# RoverBaseboard.net
KiCad netlist of a schematic drawn in EAGLE
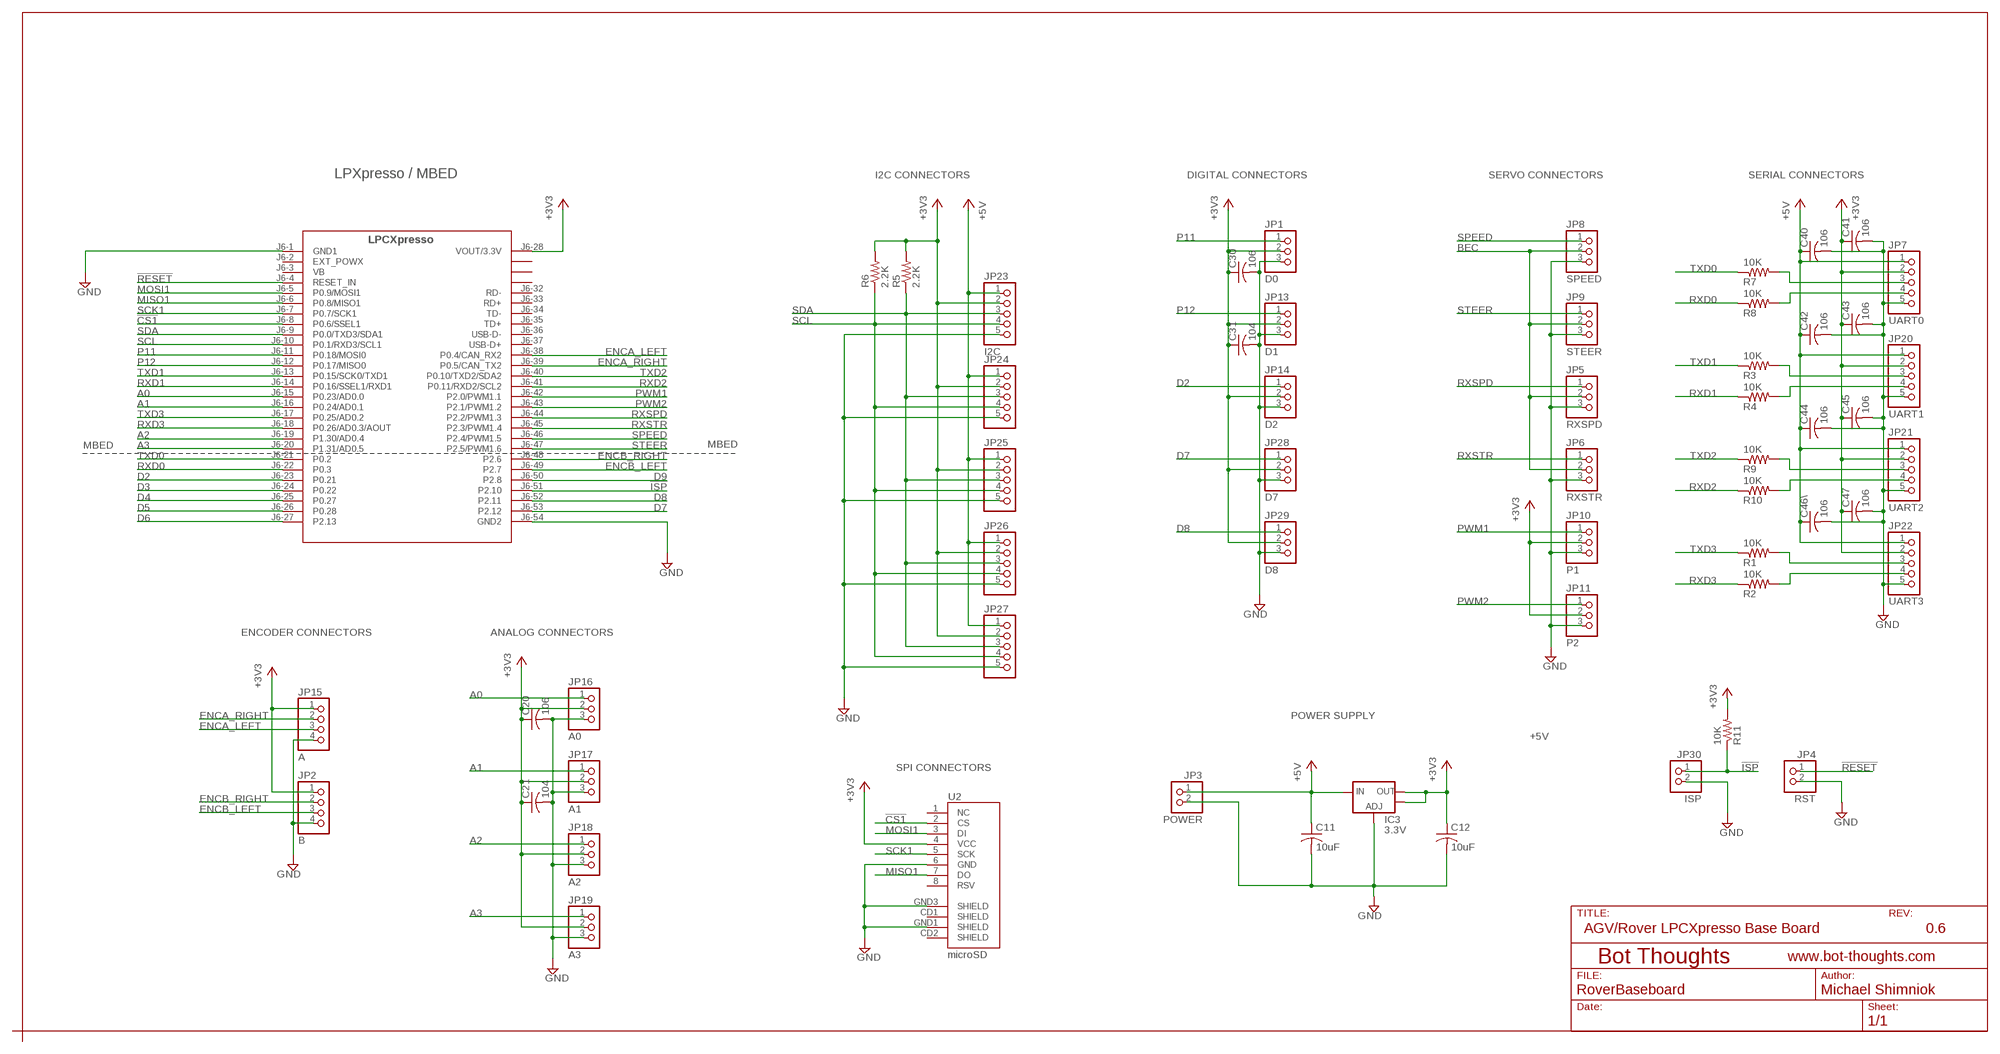
[diagram p0: schematic, sheet 1]

(export (version "E")
  (design (tool "Eeschema 10.0.6"))
  (components
    (comp (ref "C11")
      (value "10uF")
      (footprint "eagle-import:C1206")
      (libsource (lib "eagle-import") (part "C-USC1206"))
    )
    (comp (ref "C12")
      (value "10uF")
      (footprint "eagle-import:C1206")
      (libsource (lib "eagle-import") (part "C-USC1206"))
    )
    (comp (ref "C20")
      (value "106")
      (footprint "eagle-import:C0603")
      (libsource (lib "eagle-import") (part "C-USC0603"))
    )
    (comp (ref "C21")
      (value "104")
      (footprint "eagle-import:C0603")
      (libsource (lib "eagle-import") (part "C-USC0603"))
    )
    (comp (ref "C30")
      (value "106")
      (footprint "eagle-import:C0603")
      (libsource (lib "eagle-import") (part "C-USC0603"))
    )
    (comp (ref "C31")
      (value "104")
      (footprint "eagle-import:C0603")
      (libsource (lib "eagle-import") (part "C-USC0603"))
    )
    (comp (ref "C40")
      (value "106")
      (footprint "eagle-import:C0603")
      (libsource (lib "eagle-import") (part "C-USC0603"))
    )
    (comp (ref "C41")
      (value "106")
      (footprint "eagle-import:C0603")
      (libsource (lib "eagle-import") (part "C-USC0603"))
    )
    (comp (ref "C42")
      (value "106")
      (footprint "eagle-import:C0603")
      (libsource (lib "eagle-import") (part "C-USC0603"))
    )
    (comp (ref "C43")
      (value "106")
      (footprint "eagle-import:C0603")
      (libsource (lib "eagle-import") (part "C-USC0603"))
    )
    (comp (ref "C44")
      (value "106")
      (footprint "eagle-import:C0603")
      (libsource (lib "eagle-import") (part "C-USC0603"))
    )
    (comp (ref "C45")
      (value "106")
      (footprint "eagle-import:C0603")
      (libsource (lib "eagle-import") (part "C-USC0603"))
    )
    (comp (ref "C46\\")
      (value "106")
      (footprint "eagle-import:C0603")
      (libsource (lib "eagle-import") (part "C-USC0603"))
    )
    (comp (ref "C47")
      (value "106")
      (footprint "eagle-import:C0603")
      (libsource (lib "eagle-import") (part "C-USC0603"))
    )
    (comp (ref "IC3")
      (value "3.3V")
      (footprint "eagle-import:SOT223")
      (libsource (lib "eagle-import") (part "V_REG_LM1117SOT223"))
    )
    (comp (ref "JP1")
      (value "D0")
      (footprint "eagle-import:1X03-S")
      (libsource (lib "eagle-import") (part "PINHD-1X03_2.54-S"))
    )
    (comp (ref "JP2")
      (value "B")
      (footprint "eagle-import:1X04-S")
      (libsource (lib "eagle-import") (part "PINHD-1X04_2.54-S"))
    )
    (comp (ref "JP3")
      (value "POWER")
      (footprint "eagle-import:1X02-S")
      (libsource (lib "eagle-import") (part "PINHD-1X02_2.54-S"))
    )
    (comp (ref "JP4")
      (value "RST")
      (footprint "eagle-import:1X02-S")
      (libsource (lib "eagle-import") (part "PINHD-1X02_2.54-S"))
    )
    (comp (ref "JP5")
      (value "RXSPD")
      (footprint "eagle-import:1X03-S")
      (libsource (lib "eagle-import") (part "PINHD-1X03_2.54-S"))
    )
    (comp (ref "JP6")
      (value "RXSTR")
      (footprint "eagle-import:1X03-S")
      (libsource (lib "eagle-import") (part "PINHD-1X03_2.54-S"))
    )
    (comp (ref "JP7")
      (value "UART0")
      (footprint "eagle-import:1X05-S")
      (libsource (lib "eagle-import") (part "PINHD-1X05_2.54-S"))
    )
    (comp (ref "JP8")
      (value "SPEED")
      (footprint "eagle-import:1X03-S")
      (libsource (lib "eagle-import") (part "PINHD-1X03_2.54-S"))
    )
    (comp (ref "JP9")
      (value "STEER")
      (footprint "eagle-import:1X03-S")
      (libsource (lib "eagle-import") (part "PINHD-1X03_2.54-S"))
    )
    (comp (ref "JP10")
      (value "P1")
      (footprint "eagle-import:1X03-S")
      (libsource (lib "eagle-import") (part "PINHD-1X03_2.54-S"))
    )
    (comp (ref "JP11")
      (value "P2")
      (footprint "eagle-import:1X03-S")
      (libsource (lib "eagle-import") (part "PINHD-1X03_2.54-S"))
    )
    (comp (ref "JP13")
      (value "D1")
      (footprint "eagle-import:1X03-S")
      (libsource (lib "eagle-import") (part "PINHD-1X03_2.54-S"))
    )
    (comp (ref "JP14")
      (value "D2")
      (footprint "eagle-import:1X03-S")
      (libsource (lib "eagle-import") (part "PINHD-1X03_2.54-S"))
    )
    (comp (ref "JP15")
      (value "A")
      (footprint "eagle-import:1X04-S")
      (libsource (lib "eagle-import") (part "PINHD-1X04_2.54-S"))
    )
    (comp (ref "JP16")
      (value "A0")
      (footprint "eagle-import:1X03-S")
      (libsource (lib "eagle-import") (part "PINHD-1X03_2.54-S"))
    )
    (comp (ref "JP17")
      (value "A1")
      (footprint "eagle-import:1X03-S")
      (libsource (lib "eagle-import") (part "PINHD-1X03_2.54-S"))
    )
    (comp (ref "JP18")
      (value "A2")
      (footprint "eagle-import:1X03-S")
      (libsource (lib "eagle-import") (part "PINHD-1X03_2.54-S"))
    )
    (comp (ref "JP19")
      (value "A3")
      (footprint "eagle-import:1X03-S")
      (libsource (lib "eagle-import") (part "PINHD-1X03_2.54-S"))
    )
    (comp (ref "JP20")
      (value "UART1")
      (footprint "eagle-import:1X05-S")
      (libsource (lib "eagle-import") (part "PINHD-1X05_2.54-S"))
    )
    (comp (ref "JP21")
      (value "UART2")
      (footprint "eagle-import:1X05-S")
      (libsource (lib "eagle-import") (part "PINHD-1X05_2.54-S"))
    )
    (comp (ref "JP22")
      (value "UART3")
      (footprint "eagle-import:1X05-S")
      (libsource (lib "eagle-import") (part "PINHD-1X05_2.54-S"))
    )
    (comp (ref "JP23")
      (value "I2C")
      (footprint "eagle-import:1X05-S")
      (libsource (lib "eagle-import") (part "PINHD-1X05_2.54-S"))
    )
    (comp (ref "JP24")
      (value "PINHD-1X05_2.54-S")
      (footprint "eagle-import:1X05-S")
      (libsource (lib "eagle-import") (part "PINHD-1X05_2.54-S"))
    )
    (comp (ref "JP25")
      (value "PINHD-1X05_2.54-S")
      (footprint "eagle-import:1X05-S")
      (libsource (lib "eagle-import") (part "PINHD-1X05_2.54-S"))
    )
    (comp (ref "JP26")
      (value "PINHD-1X05_2.54-S")
      (footprint "eagle-import:1X05-S")
      (libsource (lib "eagle-import") (part "PINHD-1X05_2.54-S"))
    )
    (comp (ref "JP27")
      (value "PINHD-1X05_2.54-S")
      (footprint "eagle-import:1X05-S")
      (libsource (lib "eagle-import") (part "PINHD-1X05_2.54-S"))
    )
    (comp (ref "JP28")
      (value "D7")
      (footprint "eagle-import:1X03-S")
      (libsource (lib "eagle-import") (part "PINHD-1X03_2.54-S"))
    )
    (comp (ref "JP29")
      (value "D8")
      (footprint "eagle-import:1X03-S")
      (libsource (lib "eagle-import") (part "PINHD-1X03_2.54-S"))
    )
    (comp (ref "JP30")
      (value "ISP")
      (footprint "eagle-import:1X02-S")
      (libsource (lib "eagle-import") (part "PINHD-1X02_2.54-S"))
    )
    (comp (ref "R1")
      (value "10K")
      (footprint "eagle-import:R0603")
      (fields (field (name "MPN") "WCR0805-220RFI"))
      (libsource (lib "eagle-import") (part "R-US_R0603"))
    )
    (comp (ref "R2")
      (value "10K")
      (footprint "eagle-import:R0603")
      (fields (field (name "MPN") "WCR0805-220RFI"))
      (libsource (lib "eagle-import") (part "R-US_R0603"))
    )
    (comp (ref "R3")
      (value "10K")
      (footprint "eagle-import:R0603")
      (fields (field (name "MPN") "WCR0805-220RFI"))
      (libsource (lib "eagle-import") (part "R-US_R0603"))
    )
    (comp (ref "R4")
      (value "10K")
      (footprint "eagle-import:R0603")
      (fields (field (name "MPN") "WCR0805-220RFI"))
      (libsource (lib "eagle-import") (part "R-US_R0603"))
    )
    (comp (ref "R5")
      (value "2.2K")
      (footprint "eagle-import:R0603")
      (libsource (lib "eagle-import") (part "R-US_R0603"))
    )
    (comp (ref "R6")
      (value "2.2K")
      (footprint "eagle-import:R0603")
      (libsource (lib "eagle-import") (part "R-US_R0603"))
    )
    (comp (ref "R7")
      (value "10K")
      (footprint "eagle-import:R0603")
      (fields (field (name "MPN") "WCR0805-220RFI"))
      (libsource (lib "eagle-import") (part "R-US_R0603"))
    )
    (comp (ref "R8")
      (value "10K")
      (footprint "eagle-import:R0603")
      (fields (field (name "MPN") "WCR0805-220RFI"))
      (libsource (lib "eagle-import") (part "R-US_R0603"))
    )
    (comp (ref "R9")
      (value "10K")
      (footprint "eagle-import:R0603")
      (fields (field (name "MPN") "WCR0805-220RFI"))
      (libsource (lib "eagle-import") (part "R-US_R0603"))
    )
    (comp (ref "R10")
      (value "10K")
      (footprint "eagle-import:R0603")
      (fields (field (name "MPN") "WCR0805-220RFI"))
      (libsource (lib "eagle-import") (part "R-US_R0603"))
    )
    (comp (ref "R11")
      (value "10K")
      (footprint "eagle-import:R0603")
      (fields (field (name "MPN") "WCR0805-220RFI"))
      (libsource (lib "eagle-import") (part "R-US_R0603"))
    )
    (comp (ref "U$1")
      (value "LPCXPRESSO")
      (footprint "eagle-import:LPCXPRESSO_NO_PAD")
      (libsource (lib "eagle-import") (part "LPCXPRESSO_NO_PAD_1768_REVB"))
    )
    (comp (ref "U2")
      (value "microSD")
      (footprint "eagle-import:MICRO-SD-SOCKET-PP")
      (libsource (lib "eagle-import") (part "USD-SOCKETNEW"))
    )
  )
  (nets
    (net (code "1") (name "+3V3") (class "Default")
      (node (ref "C12") (pin "1") (pinfunction "1_1") (pintype "passive"))
      (node (ref "C20") (pin "1") (pinfunction "1_1") (pintype "passive"))
      (node (ref "C21") (pin "1") (pinfunction "1_1") (pintype "passive"))
      (node (ref "C30") (pin "1") (pinfunction "1_1") (pintype "passive"))
      (node (ref "C31") (pin "1") (pinfunction "1_1") (pintype "passive"))
      (node (ref "C41") (pin "1") (pinfunction "1_1") (pintype "passive"))
      (node (ref "C43") (pin "1") (pinfunction "1_1") (pintype "passive"))
      (node (ref "C45") (pin "1") (pinfunction "1_1") (pintype "passive"))
      (node (ref "C47") (pin "1") (pinfunction "1_1") (pintype "passive"))
      (node (ref "IC3") (pin "2") (pinfunction "OUT_2") (pintype "output"))
      (node (ref "IC3") (pin "4") (pinfunction "OUT_4") (pintype "output"))
      (node (ref "JP1") (pin "2") (pinfunction "2_2") (pintype "passive"))
      (node (ref "JP10") (pin "2") (pinfunction "2_2") (pintype "passive"))
      (node (ref "JP11") (pin "2") (pinfunction "2_2") (pintype "passive"))
      (node (ref "JP13") (pin "2") (pinfunction "2_2") (pintype "passive"))
      (node (ref "JP14") (pin "2") (pinfunction "2_2") (pintype "passive"))
      (node (ref "JP15") (pin "1") (pinfunction "1_1") (pintype "passive"))
      (node (ref "JP16") (pin "2") (pinfunction "2_2") (pintype "passive"))
      (node (ref "JP17") (pin "2") (pinfunction "2_2") (pintype "passive"))
      (node (ref "JP18") (pin "2") (pinfunction "2_2") (pintype "passive"))
      (node (ref "JP19") (pin "2") (pinfunction "2_2") (pintype "passive"))
      (node (ref "JP2") (pin "1") (pinfunction "1_1") (pintype "passive"))
      (node (ref "JP20") (pin "2") (pinfunction "2_2") (pintype "passive"))
      (node (ref "JP21") (pin "2") (pinfunction "2_2") (pintype "passive"))
      (node (ref "JP22") (pin "2") (pinfunction "2_2") (pintype "passive"))
      (node (ref "JP23") (pin "2") (pinfunction "2_2") (pintype "passive"))
      (node (ref "JP24") (pin "2") (pinfunction "2_2") (pintype "passive"))
      (node (ref "JP25") (pin "2") (pinfunction "2_2") (pintype "passive"))
      (node (ref "JP26") (pin "2") (pinfunction "2_2") (pintype "passive"))
      (node (ref "JP27") (pin "2") (pinfunction "2_2") (pintype "passive"))
      (node (ref "JP28") (pin "2") (pinfunction "2_2") (pintype "passive"))
      (node (ref "JP29") (pin "2") (pinfunction "2_2") (pintype "passive"))
      (node (ref "JP7") (pin "2") (pinfunction "2_2") (pintype "passive"))
      (node (ref "R11") (pin "2") (pinfunction "2_2") (pintype "passive"))
      (node (ref "R5") (pin "2") (pinfunction "2_2") (pintype "passive"))
      (node (ref "R6") (pin "2") (pinfunction "2_2") (pintype "passive"))
      (node (ref "U$1") (pin "J6-28") (pinfunction "VOUT/3.3V_J6-28") (pintype "bidirectional"))
      (node (ref "U2") (pin "4") (pinfunction "VCC_4") (pintype "bidirectional"))
    )
    (net (code "2") (name "+5V") (class "Default")
      (node (ref "C11") (pin "1") (pinfunction "1_1") (pintype "passive"))
      (node (ref "C40") (pin "1") (pinfunction "1_1") (pintype "passive"))
      (node (ref "C42") (pin "1") (pinfunction "1_1") (pintype "passive"))
      (node (ref "C44") (pin "1") (pinfunction "1_1") (pintype "passive"))
      (node (ref "C46\\") (pin "1") (pinfunction "1_1") (pintype "passive"))
      (node (ref "IC3") (pin "3") (pinfunction "IN_3") (pintype "input"))
      (node (ref "JP20") (pin "1") (pinfunction "1_1") (pintype "passive"))
      (node (ref "JP21") (pin "1") (pinfunction "1_1") (pintype "passive"))
      (node (ref "JP22") (pin "1") (pinfunction "1_1") (pintype "passive"))
      (node (ref "JP23") (pin "1") (pinfunction "1_1") (pintype "passive"))
      (node (ref "JP24") (pin "1") (pinfunction "1_1") (pintype "passive"))
      (node (ref "JP25") (pin "1") (pinfunction "1_1") (pintype "passive"))
      (node (ref "JP26") (pin "1") (pinfunction "1_1") (pintype "passive"))
      (node (ref "JP27") (pin "1") (pinfunction "1_1") (pintype "passive"))
      (node (ref "JP3") (pin "1") (pinfunction "1_1") (pintype "passive"))
      (node (ref "JP7") (pin "1") (pinfunction "1_1") (pintype "passive"))
    )
    (net (code "3") (name "/A0") (class "Default")
      (node (ref "JP16") (pin "1") (pinfunction "1_1") (pintype "passive"))
      (node (ref "U$1") (pin "J6-15") (pinfunction "P0.23/AD0.0_J6-15") (pintype "bidirectional"))
    )
    (net (code "4") (name "/A1") (class "Default")
      (node (ref "JP17") (pin "1") (pinfunction "1_1") (pintype "passive"))
      (node (ref "U$1") (pin "J6-16") (pinfunction "P0.24/AD0.1_J6-16") (pintype "bidirectional"))
    )
    (net (code "5") (name "/A2") (class "Default")
      (node (ref "JP18") (pin "1") (pinfunction "1_1") (pintype "passive"))
      (node (ref "U$1") (pin "J6-19") (pinfunction "P1.30/AD0.4_J6-19") (pintype "bidirectional"))
    )
    (net (code "6") (name "/A3") (class "Default")
      (node (ref "JP19") (pin "1") (pinfunction "1_1") (pintype "passive"))
      (node (ref "U$1") (pin "J6-20") (pinfunction "P1.31/AD0.5_J6-20") (pintype "bidirectional"))
    )
    (net (code "7") (name "/BEC") (class "Default")
      (node (ref "JP5") (pin "2") (pinfunction "2_2") (pintype "passive"))
      (node (ref "JP6") (pin "2") (pinfunction "2_2") (pintype "passive"))
      (node (ref "JP8") (pin "2") (pinfunction "2_2") (pintype "passive"))
      (node (ref "JP9") (pin "2") (pinfunction "2_2") (pintype "passive"))
    )
    (net (code "8") (name "/D2") (class "Default")
      (node (ref "JP14") (pin "1") (pinfunction "1_1") (pintype "passive"))
      (node (ref "U$1") (pin "J6-23") (pinfunction "P0.21_J6-23") (pintype "bidirectional"))
    )
    (net (code "9") (name "/D3") (class "Default")
      (node (ref "U$1") (pin "J6-24") (pinfunction "P0.22_J6-24") (pintype "bidirectional"))
    )
    (net (code "10") (name "/D4") (class "Default")
      (node (ref "U$1") (pin "J6-25") (pinfunction "P0.27_J6-25") (pintype "bidirectional"))
    )
    (net (code "11") (name "/D5") (class "Default")
      (node (ref "U$1") (pin "J6-26") (pinfunction "P0.28_J6-26") (pintype "bidirectional"))
    )
    (net (code "12") (name "/D6") (class "Default")
      (node (ref "U$1") (pin "J6-27") (pinfunction "P2.13_J6-27") (pintype "bidirectional"))
    )
    (net (code "13") (name "/D7") (class "Default")
      (node (ref "JP28") (pin "1") (pinfunction "1_1") (pintype "passive"))
      (node (ref "U$1") (pin "J6-53") (pinfunction "P2.12_J6-53") (pintype "bidirectional"))
    )
    (net (code "14") (name "/D8") (class "Default")
      (node (ref "JP29") (pin "1") (pinfunction "1_1") (pintype "passive"))
      (node (ref "U$1") (pin "J6-52") (pinfunction "P2.11_J6-52") (pintype "bidirectional"))
    )
    (net (code "15") (name "/D9") (class "Default")
      (node (ref "U$1") (pin "J6-50") (pinfunction "P2.8_J6-50") (pintype "bidirectional"))
    )
    (net (code "16") (name "/ENCA_LEFT") (class "Default")
      (node (ref "JP15") (pin "3") (pinfunction "3_3") (pintype "passive"))
      (node (ref "U$1") (pin "J6-38") (pinfunction "P0.4/CAN_RX2_J6-38") (pintype "bidirectional"))
    )
    (net (code "17") (name "/ENCA_RIGHT") (class "Default")
      (node (ref "JP15") (pin "2") (pinfunction "2_2") (pintype "passive"))
      (node (ref "U$1") (pin "J6-39") (pinfunction "P0.5/CAN_TX2_J6-39") (pintype "bidirectional"))
    )
    (net (code "18") (name "/ENCB_LEFT") (class "Default")
      (node (ref "JP2") (pin "3") (pinfunction "3_3") (pintype "passive"))
      (node (ref "U$1") (pin "J6-49") (pinfunction "P2.7_J6-49") (pintype "bidirectional"))
    )
    (net (code "19") (name "/ENCB_RIGHT") (class "Default")
      (node (ref "JP2") (pin "2") (pinfunction "2_2") (pintype "passive"))
      (node (ref "U$1") (pin "J6-48") (pinfunction "P2.6_J6-48") (pintype "bidirectional"))
    )
    (net (code "20") (name "/MISO1") (class "Default")
      (node (ref "U$1") (pin "J6-6") (pinfunction "P0.8/MISO1_J6-6") (pintype "bidirectional"))
      (node (ref "U2") (pin "7") (pinfunction "DO_7") (pintype "bidirectional"))
    )
    (net (code "21") (name "/MOSI1") (class "Default")
      (node (ref "U$1") (pin "J6-5") (pinfunction "P0.9/MOSI1_J6-5") (pintype "bidirectional"))
      (node (ref "U2") (pin "3") (pinfunction "DI_3") (pintype "bidirectional"))
    )
    (net (code "22") (name "/P11") (class "Default")
      (node (ref "JP1") (pin "1") (pinfunction "1_1") (pintype "passive"))
      (node (ref "U$1") (pin "J6-11") (pinfunction "P0.18/MOSI0_J6-11") (pintype "bidirectional"))
    )
    (net (code "23") (name "/P12") (class "Default")
      (node (ref "JP13") (pin "1") (pinfunction "1_1") (pintype "passive"))
      (node (ref "U$1") (pin "J6-12") (pinfunction "P0.17/MISO0_J6-12") (pintype "bidirectional"))
    )
    (net (code "24") (name "/PWM1") (class "Default")
      (node (ref "JP10") (pin "1") (pinfunction "1_1") (pintype "passive"))
      (node (ref "U$1") (pin "J6-42") (pinfunction "P2.0/PWM1.1_J6-42") (pintype "bidirectional"))
    )
    (net (code "25") (name "/PWM2") (class "Default")
      (node (ref "JP11") (pin "1") (pinfunction "1_1") (pintype "passive"))
      (node (ref "U$1") (pin "J6-43") (pinfunction "P2.1/PWM1.2_J6-43") (pintype "bidirectional"))
    )
    (net (code "26") (name "/RXD0") (class "Default")
      (node (ref "R8") (pin "1") (pinfunction "1_1") (pintype "passive"))
      (node (ref "U$1") (pin "J6-22") (pinfunction "P0.3_J6-22") (pintype "bidirectional"))
    )
    (net (code "27") (name "/RXD1") (class "Default")
      (node (ref "R4") (pin "1") (pinfunction "1_1") (pintype "passive"))
      (node (ref "U$1") (pin "J6-14") (pinfunction "P0.16/SSEL1/RXD1_J6-14") (pintype "bidirectional"))
    )
    (net (code "28") (name "/RXD2") (class "Default")
      (node (ref "R10") (pin "1") (pinfunction "1_1") (pintype "passive"))
      (node (ref "U$1") (pin "J6-41") (pinfunction "P0.11/RXD2/SCL2_J6-41") (pintype "bidirectional"))
    )
    (net (code "29") (name "/RXD3") (class "Default")
      (node (ref "R2") (pin "1") (pinfunction "1_1") (pintype "passive"))
      (node (ref "U$1") (pin "J6-18") (pinfunction "P0.26/AD0.3/AOUT_J6-18") (pintype "bidirectional"))
    )
    (net (code "30") (name "/RXSPD") (class "Default")
      (node (ref "JP5") (pin "1") (pinfunction "1_1") (pintype "passive"))
      (node (ref "U$1") (pin "J6-44") (pinfunction "P2.2/PWM1.3_J6-44") (pintype "bidirectional"))
    )
    (net (code "31") (name "/RXSTR") (class "Default")
      (node (ref "JP6") (pin "1") (pinfunction "1_1") (pintype "passive"))
      (node (ref "U$1") (pin "J6-45") (pinfunction "P2.3/PWM1.4_J6-45") (pintype "bidirectional"))
    )
    (net (code "32") (name "/SCK1") (class "Default")
      (node (ref "U$1") (pin "J6-7") (pinfunction "P0.7/SCK1_J6-7") (pintype "bidirectional"))
      (node (ref "U2") (pin "5") (pinfunction "SCK_5") (pintype "bidirectional"))
    )
    (net (code "33") (name "/SCL") (class "Default")
      (node (ref "JP23") (pin "4") (pinfunction "4_4") (pintype "passive"))
      (node (ref "JP24") (pin "4") (pinfunction "4_4") (pintype "passive"))
      (node (ref "JP25") (pin "4") (pinfunction "4_4") (pintype "passive"))
      (node (ref "JP26") (pin "4") (pinfunction "4_4") (pintype "passive"))
      (node (ref "JP27") (pin "4") (pinfunction "4_4") (pintype "passive"))
      (node (ref "R6") (pin "1") (pinfunction "1_1") (pintype "passive"))
      (node (ref "U$1") (pin "J6-10") (pinfunction "P0.1/RXD3/SCL1_J6-10") (pintype "bidirectional"))
    )
    (net (code "34") (name "/SDA") (class "Default")
      (node (ref "JP23") (pin "3") (pinfunction "3_3") (pintype "passive"))
      (node (ref "JP24") (pin "3") (pinfunction "3_3") (pintype "passive"))
      (node (ref "JP25") (pin "3") (pinfunction "3_3") (pintype "passive"))
      (node (ref "JP26") (pin "3") (pinfunction "3_3") (pintype "passive"))
      (node (ref "JP27") (pin "3") (pinfunction "3_3") (pintype "passive"))
      (node (ref "R5") (pin "1") (pinfunction "1_1") (pintype "passive"))
      (node (ref "U$1") (pin "J6-9") (pinfunction "P0.0/TXD3/SDA1_J6-9") (pintype "bidirectional"))
    )
    (net (code "35") (name "/SPEED") (class "Default")
      (node (ref "JP8") (pin "1") (pinfunction "1_1") (pintype "passive"))
      (node (ref "U$1") (pin "J6-46") (pinfunction "P2.4/PWM1.5_J6-46") (pintype "bidirectional"))
    )
    (net (code "36") (name "/STEER") (class "Default")
      (node (ref "JP9") (pin "1") (pinfunction "1_1") (pintype "passive"))
      (node (ref "U$1") (pin "J6-47") (pinfunction "P2.5/PWM1.6_J6-47") (pintype "bidirectional"))
    )
    (net (code "37") (name "/TXD0") (class "Default")
      (node (ref "R7") (pin "1") (pinfunction "1_1") (pintype "passive"))
      (node (ref "U$1") (pin "J6-21") (pinfunction "P0.2_J6-21") (pintype "bidirectional"))
    )
    (net (code "38") (name "/TXD1") (class "Default")
      (node (ref "R3") (pin "1") (pinfunction "1_1") (pintype "passive"))
      (node (ref "U$1") (pin "J6-13") (pinfunction "P0.15/SCK0/TXD1_J6-13") (pintype "bidirectional"))
    )
    (net (code "39") (name "/TXD2") (class "Default")
      (node (ref "R9") (pin "1") (pinfunction "1_1") (pintype "passive"))
      (node (ref "U$1") (pin "J6-40") (pinfunction "P0.10/TXD2/SDA2_J6-40") (pintype "bidirectional"))
    )
    (net (code "40") (name "/TXD3") (class "Default")
      (node (ref "R1") (pin "1") (pinfunction "1_1") (pintype "passive"))
      (node (ref "U$1") (pin "J6-17") (pinfunction "P0.25/AD0.2_J6-17") (pintype "bidirectional"))
    )
    (net (code "41") (name "/~{CS1}") (class "Default")
      (node (ref "U$1") (pin "J6-8") (pinfunction "P0.6/SSEL1_J6-8") (pintype "bidirectional"))
      (node (ref "U2") (pin "2") (pinfunction "CS_2") (pintype "bidirectional"))
    )
    (net (code "42") (name "/~{ISP}") (class "Default")
      (node (ref "JP30") (pin "1") (pinfunction "1_1") (pintype "passive"))
      (node (ref "R11") (pin "1") (pinfunction "1_1") (pintype "passive"))
      (node (ref "U$1") (pin "J6-51") (pinfunction "P2.10_J6-51") (pintype "bidirectional"))
    )
    (net (code "43") (name "/~{RESET}") (class "Default")
      (node (ref "JP4") (pin "1") (pinfunction "1_1") (pintype "passive"))
      (node (ref "U$1") (pin "J6-4") (pinfunction "RESET_IN_J6-4") (pintype "bidirectional"))
    )
    (net (code "44") (name "GND") (class "Default")
      (node (ref "C11") (pin "2") (pinfunction "2_2") (pintype "passive"))
      (node (ref "C12") (pin "2") (pinfunction "2_2") (pintype "passive"))
      (node (ref "C20") (pin "2") (pinfunction "2_2") (pintype "passive"))
      (node (ref "C21") (pin "2") (pinfunction "2_2") (pintype "passive"))
      (node (ref "C30") (pin "2") (pinfunction "2_2") (pintype "passive"))
      (node (ref "C31") (pin "2") (pinfunction "2_2") (pintype "passive"))
      (node (ref "C40") (pin "2") (pinfunction "2_2") (pintype "passive"))
      (node (ref "C41") (pin "2") (pinfunction "2_2") (pintype "passive"))
      (node (ref "C42") (pin "2") (pinfunction "2_2") (pintype "passive"))
      (node (ref "C43") (pin "2") (pinfunction "2_2") (pintype "passive"))
      (node (ref "C44") (pin "2") (pinfunction "2_2") (pintype "passive"))
      (node (ref "C45") (pin "2") (pinfunction "2_2") (pintype "passive"))
      (node (ref "C46\\") (pin "2") (pinfunction "2_2") (pintype "passive"))
      (node (ref "C47") (pin "2") (pinfunction "2_2") (pintype "passive"))
      (node (ref "IC3") (pin "1") (pinfunction "ADJ_1") (pintype "input"))
      (node (ref "JP1") (pin "3") (pinfunction "3_3") (pintype "passive"))
      (node (ref "JP10") (pin "3") (pinfunction "3_3") (pintype "passive"))
      (node (ref "JP11") (pin "3") (pinfunction "3_3") (pintype "passive"))
      (node (ref "JP13") (pin "3") (pinfunction "3_3") (pintype "passive"))
      (node (ref "JP14") (pin "3") (pinfunction "3_3") (pintype "passive"))
      (node (ref "JP15") (pin "4") (pinfunction "4_4") (pintype "passive"))
      (node (ref "JP16") (pin "3") (pinfunction "3_3") (pintype "passive"))
      (node (ref "JP17") (pin "3") (pinfunction "3_3") (pintype "passive"))
      (node (ref "JP18") (pin "3") (pinfunction "3_3") (pintype "passive"))
      (node (ref "JP19") (pin "3") (pinfunction "3_3") (pintype "passive"))
      (node (ref "JP2") (pin "4") (pinfunction "4_4") (pintype "passive"))
      (node (ref "JP20") (pin "5") (pinfunction "5_5") (pintype "passive"))
      (node (ref "JP21") (pin "5") (pinfunction "5_5") (pintype "passive"))
      (node (ref "JP22") (pin "5") (pinfunction "5_5") (pintype "passive"))
      (node (ref "JP23") (pin "5") (pinfunction "5_5") (pintype "passive"))
      (node (ref "JP24") (pin "5") (pinfunction "5_5") (pintype "passive"))
      (node (ref "JP25") (pin "5") (pinfunction "5_5") (pintype "passive"))
      (node (ref "JP26") (pin "5") (pinfunction "5_5") (pintype "passive"))
      (node (ref "JP27") (pin "5") (pinfunction "5_5") (pintype "passive"))
      (node (ref "JP28") (pin "3") (pinfunction "3_3") (pintype "passive"))
      (node (ref "JP29") (pin "3") (pinfunction "3_3") (pintype "passive"))
      (node (ref "JP3") (pin "2") (pinfunction "2_2") (pintype "passive"))
      (node (ref "JP30") (pin "2") (pinfunction "2_2") (pintype "passive"))
      (node (ref "JP4") (pin "2") (pinfunction "2_2") (pintype "passive"))
      (node (ref "JP5") (pin "3") (pinfunction "3_3") (pintype "passive"))
      (node (ref "JP6") (pin "3") (pinfunction "3_3") (pintype "passive"))
      (node (ref "JP7") (pin "5") (pinfunction "5_5") (pintype "passive"))
      (node (ref "JP8") (pin "3") (pinfunction "3_3") (pintype "passive"))
      (node (ref "JP9") (pin "3") (pinfunction "3_3") (pintype "passive"))
      (node (ref "U$1") (pin "J6-1") (pinfunction "GND1_J6-1") (pintype "bidirectional"))
      (node (ref "U$1") (pin "J6-54") (pinfunction "GND2_J6-54") (pintype "bidirectional"))
      (node (ref "U2") (pin "6") (pinfunction "GND_6") (pintype "bidirectional"))
      (node (ref "U2") (pin "GND1") (pinfunction "SHIELD_GND1") (pintype "bidirectional"))
      (node (ref "U2") (pin "GND3") (pinfunction "SHIELD_GND3") (pintype "bidirectional"))
    )
    (net (code "45") (name "Net-(JP7-Pad3)") (class "Default")
      (node (ref "JP7") (pin "3") (pinfunction "3_3") (pintype "passive"))
      (node (ref "R7") (pin "2") (pinfunction "2_2") (pintype "passive"))
    )
    (net (code "46") (name "Net-(JP7-Pad4)") (class "Default")
      (node (ref "JP7") (pin "4") (pinfunction "4_4") (pintype "passive"))
      (node (ref "R8") (pin "2") (pinfunction "2_2") (pintype "passive"))
    )
    (net (code "47") (name "Net-(JP20-Pad3)") (class "Default")
      (node (ref "JP20") (pin "3") (pinfunction "3_3") (pintype "passive"))
      (node (ref "R3") (pin "2") (pinfunction "2_2") (pintype "passive"))
    )
    (net (code "48") (name "Net-(JP20-Pad4)") (class "Default")
      (node (ref "JP20") (pin "4") (pinfunction "4_4") (pintype "passive"))
      (node (ref "R4") (pin "2") (pinfunction "2_2") (pintype "passive"))
    )
    (net (code "49") (name "Net-(JP21-Pad3)") (class "Default")
      (node (ref "JP21") (pin "3") (pinfunction "3_3") (pintype "passive"))
      (node (ref "R9") (pin "2") (pinfunction "2_2") (pintype "passive"))
    )
    (net (code "50") (name "Net-(JP21-Pad4)") (class "Default")
      (node (ref "JP21") (pin "4") (pinfunction "4_4") (pintype "passive"))
      (node (ref "R10") (pin "2") (pinfunction "2_2") (pintype "passive"))
    )
    (net (code "51") (name "Net-(JP22-Pad3)") (class "Default")
      (node (ref "JP22") (pin "3") (pinfunction "3_3") (pintype "passive"))
      (node (ref "R1") (pin "2") (pinfunction "2_2") (pintype "passive"))
    )
    (net (code "52") (name "Net-(JP22-Pad4)") (class "Default")
      (node (ref "JP22") (pin "4") (pinfunction "4_4") (pintype "passive"))
      (node (ref "R2") (pin "2") (pinfunction "2_2") (pintype "passive"))
    )
    (net (code "53") (name "unconnected-(U$1-EXT_POWX-PadJ6-2)") (class "Default")
      (node (ref "U$1") (pin "J6-2") (pinfunction "EXT_POWX_J6-2") (pintype "bidirectional"))
    )
    (net (code "54") (name "unconnected-(U$1-P$24-PadJ6-29)") (class "Default")
      (node (ref "U$1") (pin "J6-29") (pinfunction "P$24_J6-29") (pintype "no_connect"))
    )
    (net (code "55") (name "unconnected-(U$1-P$25-PadJ6-30)") (class "Default")
      (node (ref "U$1") (pin "J6-30") (pinfunction "P$25_J6-30") (pintype "no_connect"))
    )
    (net (code "56") (name "unconnected-(U$1-P$26-PadJ6-31)") (class "Default")
      (node (ref "U$1") (pin "J6-31") (pinfunction "P$26_J6-31") (pintype "no_connect"))
    )
    (net (code "57") (name "unconnected-(U$1-RD+-PadJ6-33)") (class "Default")
      (node (ref "U$1") (pin "J6-33") (pinfunction "RD+_J6-33") (pintype "bidirectional"))
    )
    (net (code "58") (name "unconnected-(U$1-RD--PadJ6-32)") (class "Default")
      (node (ref "U$1") (pin "J6-32") (pinfunction "RD-_J6-32") (pintype "bidirectional"))
    )
    (net (code "59") (name "unconnected-(U$1-TD+-PadJ6-35)") (class "Default")
      (node (ref "U$1") (pin "J6-35") (pinfunction "TD+_J6-35") (pintype "bidirectional"))
    )
    (net (code "60") (name "unconnected-(U$1-TD--PadJ6-34)") (class "Default")
      (node (ref "U$1") (pin "J6-34") (pinfunction "TD-_J6-34") (pintype "bidirectional"))
    )
    (net (code "61") (name "unconnected-(U$1-USB-D+-PadJ6-37)") (class "Default")
      (node (ref "U$1") (pin "J6-37") (pinfunction "USB-D+_J6-37") (pintype "bidirectional"))
    )
    (net (code "62") (name "unconnected-(U$1-USB-D--PadJ6-36)") (class "Default")
      (node (ref "U$1") (pin "J6-36") (pinfunction "USB-D-_J6-36") (pintype "bidirectional"))
    )
    (net (code "63") (name "unconnected-(U$1-VB-PadJ6-3)") (class "Default")
      (node (ref "U$1") (pin "J6-3") (pinfunction "VB_J6-3") (pintype "bidirectional"))
    )
    (net (code "64") (name "unconnected-(U2-NC-Pad1)") (class "Default")
      (node (ref "U2") (pin "1") (pinfunction "NC_1") (pintype "bidirectional"))
    )
    (net (code "65") (name "unconnected-(U2-RSV-Pad8)") (class "Default")
      (node (ref "U2") (pin "8") (pinfunction "RSV_8") (pintype "bidirectional"))
    )
    (net (code "66") (name "unconnected-(U2-SHIELD-PadCD1)") (class "Default")
      (node (ref "U2") (pin "CD1") (pinfunction "SHIELD_CD1") (pintype "bidirectional"))
    )
    (net (code "67") (name "unconnected-(U2-SHIELD-PadCD2)") (class "Default")
      (node (ref "U2") (pin "CD2") (pinfunction "SHIELD_CD2") (pintype "bidirectional"))
    )
  )
)
